# Trepanat_MCU.net
KiCad netlist of a schematic drawn in Altium Designer
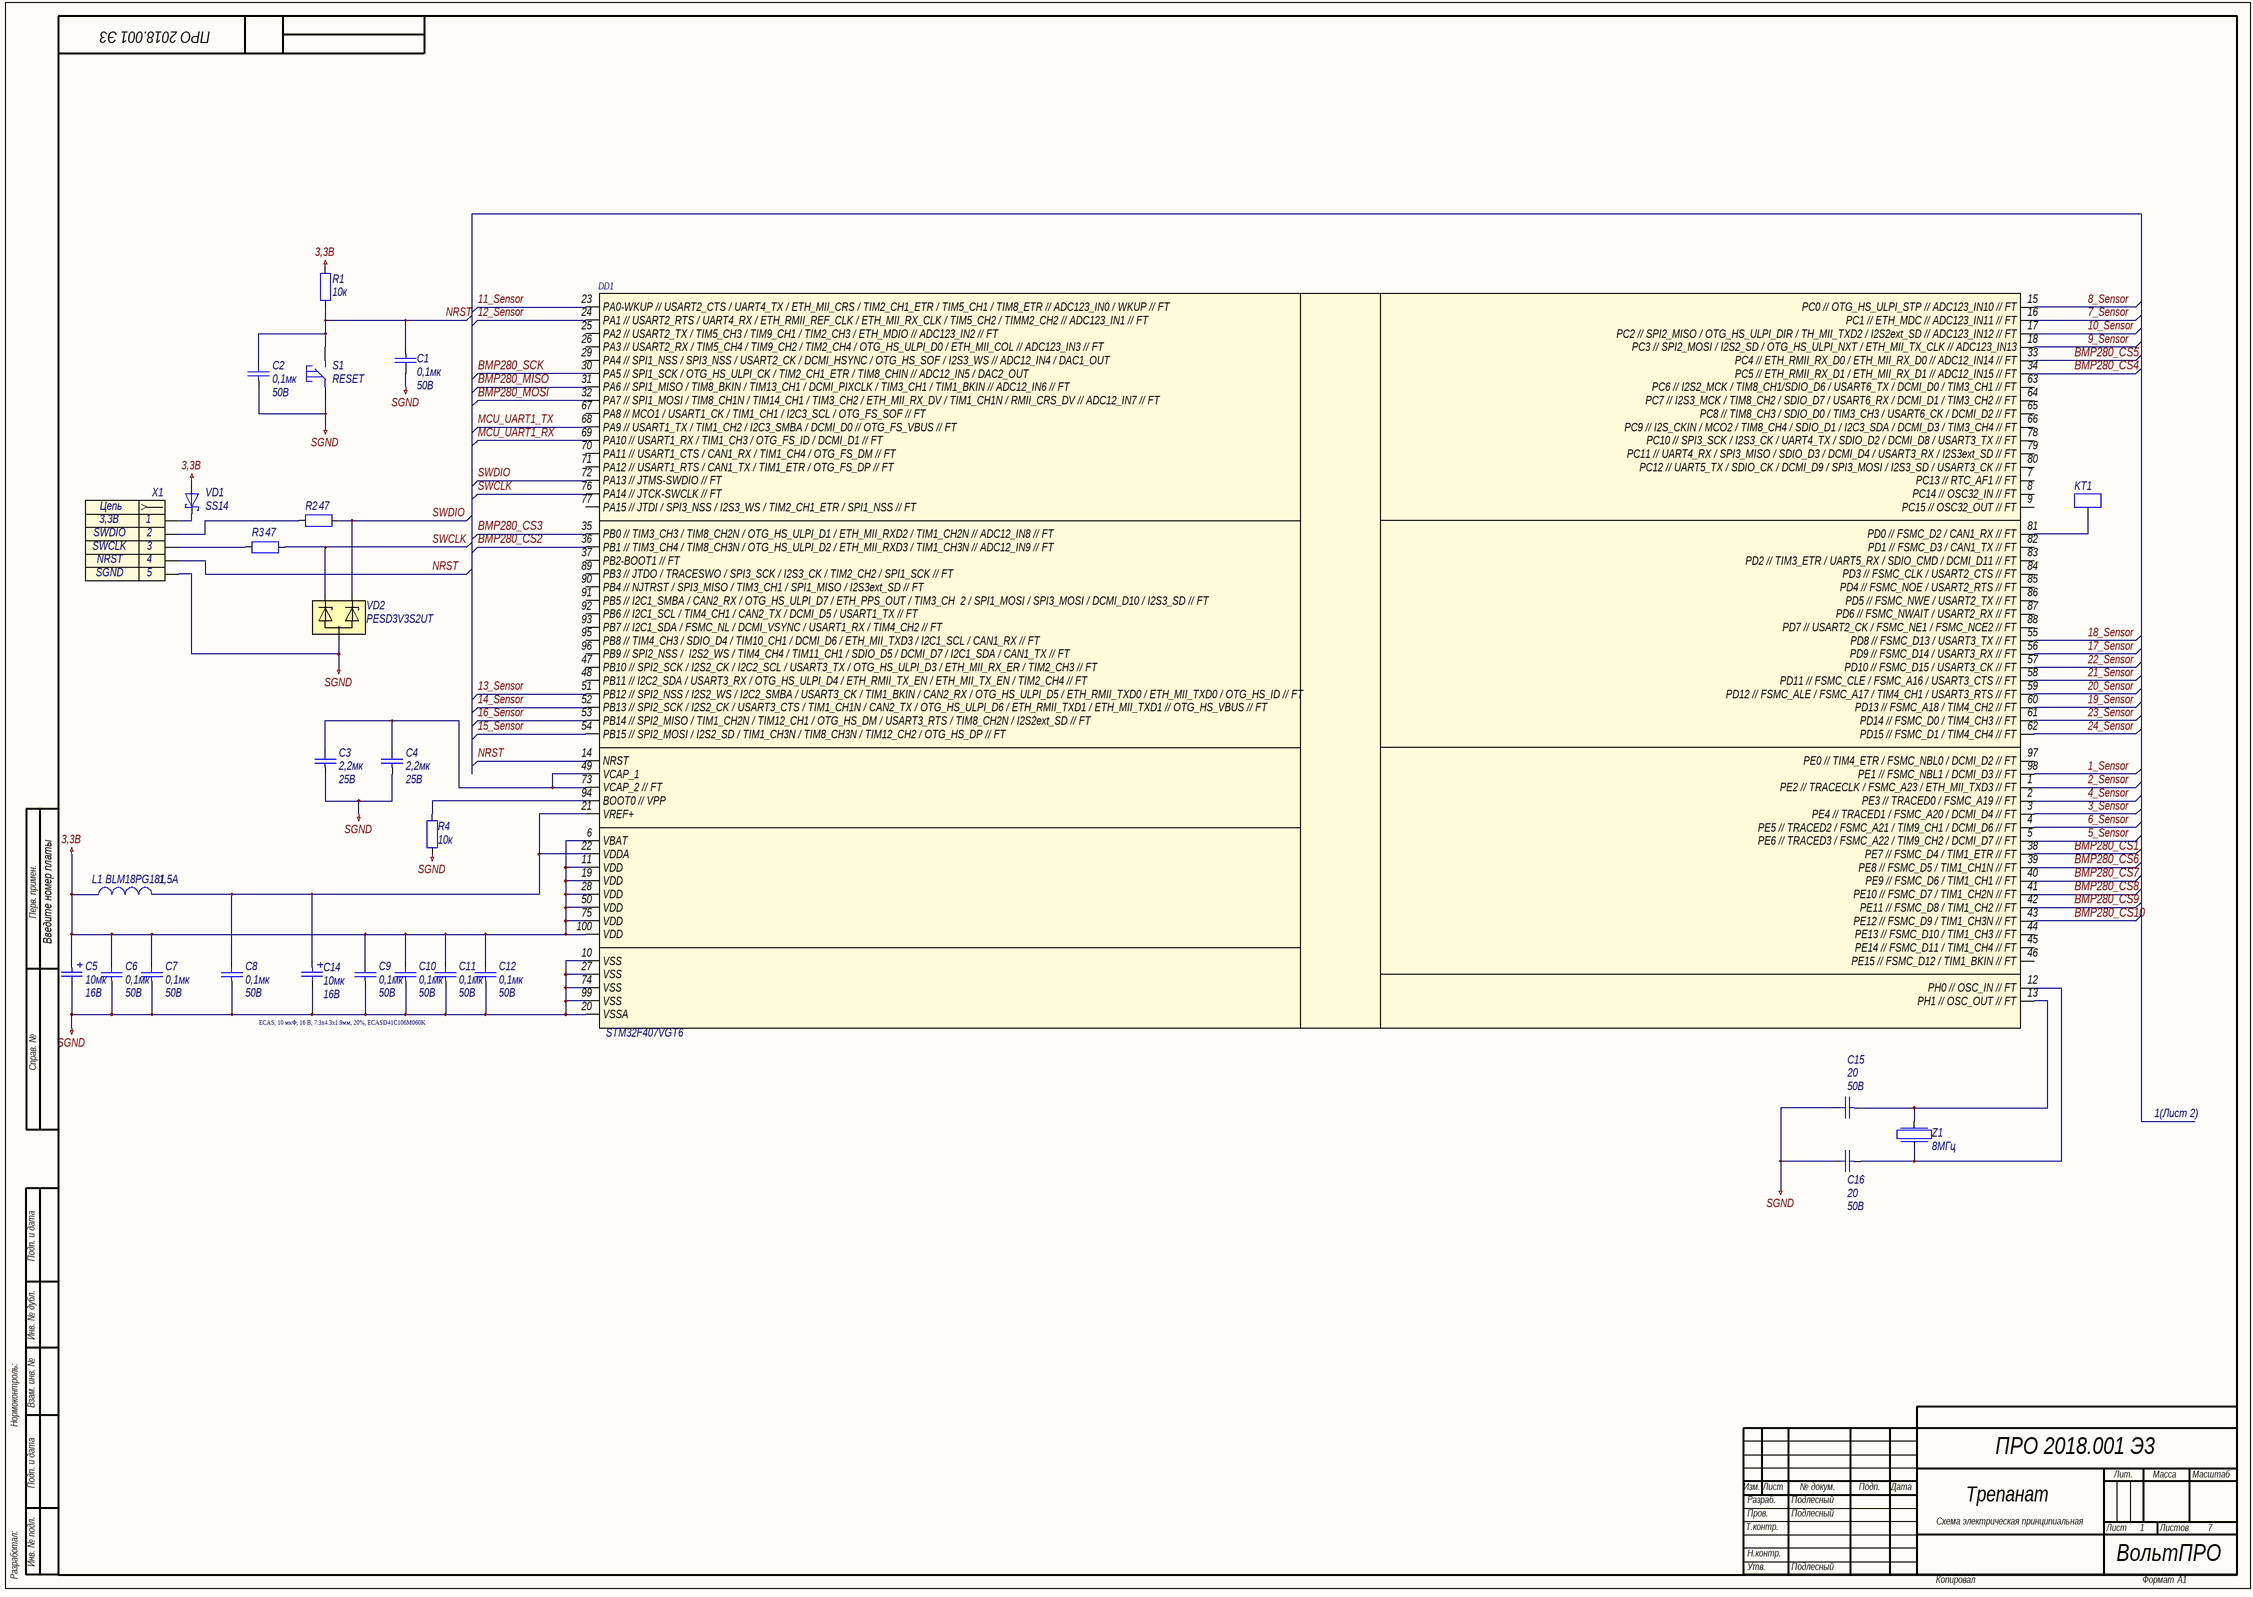
[diagram p0: Trepanat_MCU.SchDoc]

(export (version "E")
  (design (tool "Eeschema 10.0.6"))
  (components
    (comp (ref "C1")
      (value "0,1мк")
      (footprint "ZabugorLib:C0805")
      (description "Конденсатор")
      (fields (field (name "VOLTAGE") "50В"))
      (libsource (lib "ZabugorLib") (part "Capacitor"))
    )
    (comp (ref "C2")
      (value "0,1мк")
      (footprint "ZabugorLib:C0805")
      (description "Конденсатор")
      (fields (field (name "VOLTAGE") "50В"))
      (libsource (lib "ZabugorLib") (part "Capacitor"))
    )
    (comp (ref "C3")
      (value "2,2мк")
      (footprint "ZabugorLib:C0805")
      (description "Конденсатор")
      (fields (field (name "VOLTAGE") "25В"))
      (libsource (lib "ZabugorLib") (part "Capacitor"))
    )
    (comp (ref "C4")
      (value "2,2мк")
      (footprint "ZabugorLib:C0805")
      (description "Конденсатор")
      (fields (field (name "VOLTAGE") "25В"))
      (libsource (lib "ZabugorLib") (part "Capacitor"))
    )
    (comp (ref "C5")
      (value "10мк")
      (footprint "ZabugorLib:TANTAL CASE D")
      (description "Конденсатор полярный")
      (fields (field (name "VOLTAGE") "16В"))
      (libsource (lib "ZabugorLib") (part "Capacitor_pol"))
    )
    (comp (ref "C6")
      (value "0,1мк")
      (footprint "ZabugorLib:C0805")
      (description "Конденсатор")
      (fields (field (name "VOLTAGE") "50В"))
      (libsource (lib "ZabugorLib") (part "Capacitor"))
    )
    (comp (ref "C7")
      (value "0,1мк")
      (footprint "ZabugorLib:C0805")
      (description "Конденсатор")
      (fields (field (name "VOLTAGE") "50В"))
      (libsource (lib "ZabugorLib") (part "Capacitor"))
    )
    (comp (ref "C8")
      (value "0,1мк")
      (footprint "ZabugorLib:C0805")
      (description "Конденсатор")
      (fields (field (name "VOLTAGE") "50В"))
      (libsource (lib "ZabugorLib") (part "Capacitor"))
    )
    (comp (ref "C9")
      (value "0,1мк")
      (footprint "ZabugorLib:C0805")
      (description "Конденсатор")
      (fields (field (name "VOLTAGE") "50В"))
      (libsource (lib "ZabugorLib") (part "Capacitor"))
    )
    (comp (ref "C10")
      (value "0,1мк")
      (footprint "ZabugorLib:C0805")
      (description "Конденсатор")
      (fields (field (name "VOLTAGE") "50В"))
      (libsource (lib "ZabugorLib") (part "Capacitor"))
    )
    (comp (ref "C11")
      (value "0,1мк")
      (footprint "ZabugorLib:C0805")
      (description "Конденсатор")
      (fields (field (name "VOLTAGE") "50В"))
      (libsource (lib "ZabugorLib") (part "Capacitor"))
    )
    (comp (ref "C12")
      (value "0,1мк")
      (footprint "ZabugorLib:C0805")
      (description "Конденсатор")
      (fields (field (name "VOLTAGE") "50В"))
      (libsource (lib "ZabugorLib") (part "Capacitor"))
    )
    (comp (ref "C14")
      (value "10мк")
      (footprint "ZabugorLib:TANTAL CASE D")
      (description "Конденсатор полярный")
      (fields (field (name "VOLTAGE") "16В"))
      (libsource (lib "ZabugorLib") (part "Capacitor_pol"))
    )
    (comp (ref "C15")
      (value "20")
      (footprint "ZabugorLib:C0805")
      (description "Конденсатор")
      (fields (field (name "VOLTAGE") "50В"))
      (libsource (lib "ZabugorLib") (part "Capacitor"))
    )
    (comp (ref "C16")
      (value "20")
      (footprint "ZabugorLib:C0805")
      (description "Конденсатор")
      (fields (field (name "VOLTAGE") "50В"))
      (libsource (lib "ZabugorLib") (part "Capacitor"))
    )
    (comp (ref "DD1")
      (value "~")
      (footprint "ZabugorLib:LQPF100")
      (description "Микроконтроллер")
      (libsource (lib "ZabugorLib") (part "STM32F407VGT6"))
    )
    (comp (ref "KT1")
      (value "KT")
      (footprint "ZabugorLib:КТ")
      (description "Контрольная точка")
      (libsource (lib "ZabugorLib") (part "KT"))
    )
    (comp (ref "L1")
      (value "BLM18PG181")
      (footprint "ZabugorLib:L0603")
      (description "Катушка индуктивности")
      (fields (field (name "IMAX") "1,5A"))
      (libsource (lib "ZabugorLib") (part "Inductor"))
    )
    (comp (ref "R1")
      (value "10к")
      (footprint "ZabugorLib:R0805")
      (description "Резистор")
      (libsource (lib "") (part "Resistor_1"))
    )
    (comp (ref "R2")
      (value "47")
      (footprint "ZabugorLib:R0805")
      (description "Резистор")
      (libsource (lib "ZabugorLib") (part "Resistor"))
    )
    (comp (ref "R3")
      (value "47")
      (footprint "ZabugorLib:R0805")
      (description "Резистор")
      (libsource (lib "ZabugorLib") (part "Resistor"))
    )
    (comp (ref "R4")
      (value "10к")
      (footprint "ZabugorLib:R0805")
      (description "Резистор")
      (libsource (lib "") (part "Resistor_2"))
    )
    (comp (ref "S1")
      (value "RESET")
      (footprint "ZabugorLib:Button_SMD")
      (description "Кнопка")
      (fields (field (name "NAME") "RESET"))
      (libsource (lib "ZabugorLib") (part "Button_SMD"))
    )
    (comp (ref "VD1")
      (value "SS14")
      (footprint "ZabugorLib:SMA")
      (description "Диод Шоттки")
      (libsource (lib "ZabugorLib") (part "DiodeSchottky"))
    )
    (comp (ref "VD2")
      (value "PESD3V3S2UT")
      (footprint "ZabugorLib:SOT23-3")
      (description "Сборка TVS-диодов")
      (fields (field (name "NAME") "PESD3V3S2UT"))
      (libsource (lib "ZabugorLib") (part "PESD3V3S2UT"))
    )
    (comp (ref "X1")
      (value "~")
      (footprint "ZabugorLib:PLS-5")
      (description "Разъем - 4 конт. розетка")
      (libsource (lib "ZabugorLib") (part "Header_5_sct"))
    )
    (comp (ref "Z1")
      (value "8МГц")
      (footprint "ZabugorLib:QSMD5.0x3.2x1.0")
      (description "Кварцевый резонатор")
      (libsource (lib "ZabugorLib") (part "Crystal"))
    )
  )
  (nets
    (net (code "1") (name "/1_Sensor") (class "Default")
      (node (ref "DD1") (pin "98") (pinfunction "PE1_//_FSMC_NBL1_/_DCMI_D3_//_FT_98") (pintype "passive"))
    )
    (net (code "2") (name "/2_Sensor") (class "Default")
      (node (ref "DD1") (pin "1") (pinfunction "PE2_//_TRACECLK_/_FSMC_A23_/_ETH_MII_TXD3_//_FT_1") (pintype "passive"))
    )
    (net (code "3") (name "/3_Sensor") (class "Default")
      (node (ref "DD1") (pin "3") (pinfunction "PE4_//_TRACED1_/_FSMC_A20_/_DCMI_D4_//_FT_3") (pintype "passive"))
    )
    (net (code "4") (name "/4_Sensor") (class "Default")
      (node (ref "DD1") (pin "2") (pinfunction "PE3_//_TRACED0_/_FSMC_A19_//_FT_2") (pintype "passive"))
    )
    (net (code "5") (name "/5_Sensor") (class "Default")
      (node (ref "DD1") (pin "5") (pinfunction "PE6_//_TRACED3_/_FSMC_A22_/_TIM9_CH2_/_DCMI_D7_//_FT_5") (pintype "passive"))
    )
    (net (code "6") (name "/6_Sensor") (class "Default")
      (node (ref "DD1") (pin "4") (pinfunction "PE5_//_TRACED2_/_FSMC_A21_/_TIM9_CH1_/_DCMI_D6_//_FT_4") (pintype "passive"))
    )
    (net (code "7") (name "/7_Sensor") (class "Default")
      (node (ref "DD1") (pin "16") (pinfunction "PC1_//_ETH_MDC_//_ADC123_IN11_//_FT_16") (pintype "passive"))
    )
    (net (code "8") (name "/8_Sensor") (class "Default")
      (node (ref "DD1") (pin "15") (pinfunction "PC0_//_OTG_HS_ULPI_STP_//_ADC123_IN10_//_FT_15") (pintype "passive"))
    )
    (net (code "9") (name "/9_Sensor") (class "Default")
      (node (ref "DD1") (pin "18") (pinfunction "PC3_//_SPI2_MOSI_/_I2S2_SD_/_OTG_HS_ULPI_NXT_/_ETH_MII_TX_CLK_//_ADC123_IN13_18") (pintype "passive"))
    )
    (net (code "10") (name "/10_Sensor") (class "Default")
      (node (ref "DD1") (pin "17") (pinfunction "PC2_//_SPI2_MISO_/_OTG_HS_ULPI_DIR_/_TH_MII_TXD2_/_I2S2ext_SD_//_ADC123_IN12_//_FT_17") (pintype "passive"))
    )
    (net (code "11") (name "/11_Sensor") (class "Default")
      (node (ref "DD1") (pin "23") (pinfunction "PA0-WKUP_//_USART2_CTS_/_UART4_TX_/_ETH_MII_CRS_/_TIM2_CH1_ETR_/_TIM5_CH1_/_TIM8_ETR_//_ADC123_IN0_/_WKUP_//_FT_23") (pintype "passive"))
    )
    (net (code "12") (name "/12_Sensor") (class "Default")
      (node (ref "DD1") (pin "24") (pinfunction "PA1_//_USART2_RTS_/_UART4_RX_/_ETH_RMII_REF_CLK_/_ETH_MII_RX_CLK_/_TIM5_CH2_/_TIMM2_CH2_//_ADC123_IN1_//_FT_24") (pintype "passive"))
    )
    (net (code "13") (name "/13_Sensor") (class "Default")
      (node (ref "DD1") (pin "51") (pinfunction "PB12_//_SPI2_NSS_/_I2S2_WS_/_I2C2_SMBA_/_USART3_CK_/_TIM1_BKIN_/_CAN2_RX_/_OTG_HS_ULPI_D5_/_ETH_RMII_TXD0_/_ETH_MII_TXD0_/_OTG_HS_ID_//_FT_51") (pintype "passive"))
    )
    (net (code "14") (name "/14_Sensor") (class "Default")
      (node (ref "DD1") (pin "52") (pinfunction "PB13_//_SPI2_SCK_/_I2S2_CK_/_USART3_CTS_/_TIM1_CH1N_/_CAN2_TX_/_OTG_HS_ULPI_D6_/_ETH_RMII_TXD1_/_ETH_MII_TXD1_//_OTG_HS_VBUS_//_FT_52") (pintype "passive"))
    )
    (net (code "15") (name "/15_Sensor") (class "Default")
      (node (ref "DD1") (pin "54") (pinfunction "PB15_//_SPI2_MOSI_/_I2S2_SD_/_TIM1_CH3N_/_TIM8_CH3N_/_TIM12_CH2_/_OTG_HS_DP_//_FT_54") (pintype "passive"))
    )
    (net (code "16") (name "/16_Sensor") (class "Default")
      (node (ref "DD1") (pin "53") (pinfunction "PB14_//_SPI2_MISO_/_TIM1_CH2N_/_TIM12_CH1_/_OTG_HS_DM_/_USART3_RTS_/_TIM8_CH2N_/_I2S2ext_SD_//_FT_53") (pintype "passive"))
    )
    (net (code "17") (name "/17_Sensor") (class "Default")
      (node (ref "DD1") (pin "56") (pinfunction "PD9_//_FSMC_D14_/_USART3_RX_//_FT_56") (pintype "passive"))
    )
    (net (code "18") (name "/18_Sensor") (class "Default")
      (node (ref "DD1") (pin "55") (pinfunction "PD8_//_FSMC_D13_/_USART3_TX_//_FT_55") (pintype "passive"))
    )
    (net (code "19") (name "/19_Sensor") (class "Default")
      (node (ref "DD1") (pin "60") (pinfunction "PD13_//_FSMC_A18_/_TIM4_CH2_//_FT_60") (pintype "passive"))
    )
    (net (code "20") (name "/20_Sensor") (class "Default")
      (node (ref "DD1") (pin "59") (pinfunction "PD12_//_FSMC_ALE_/_FSMC_A17_/_TIM4_CH1_/_USART3_RTS_//_FT_59") (pintype "passive"))
    )
    (net (code "21") (name "/21_Sensor") (class "Default")
      (node (ref "DD1") (pin "58") (pinfunction "PD11_//_FSMC_CLE_/_FSMC_A16_/_USART3_CTS_//_FT_58") (pintype "passive"))
    )
    (net (code "22") (name "/22_Sensor") (class "Default")
      (node (ref "DD1") (pin "57") (pinfunction "PD10_//_FSMC_D15_/_USART3_CK_//_FT_57") (pintype "passive"))
    )
    (net (code "23") (name "/23_Sensor") (class "Default")
      (node (ref "DD1") (pin "61") (pinfunction "PD14_//_FSMC_D0_/_TIM4_CH3_//_FT_61") (pintype "passive"))
    )
    (net (code "24") (name "/24_Sensor") (class "Default")
      (node (ref "DD1") (pin "62") (pinfunction "PD15_//_FSMC_D1_/_TIM4_CH4_//_FT_62") (pintype "passive"))
    )
    (net (code "25") (name "/BMP280_CS1") (class "Default")
      (node (ref "DD1") (pin "38") (pinfunction "PE7_//_FSMC_D4_/_TIM1_ETR_//_FT_38") (pintype "passive"))
    )
    (net (code "26") (name "/BMP280_CS2") (class "Default")
      (node (ref "DD1") (pin "36") (pinfunction "PB1_//_TIM3_CH4_/_TIM8_CH3N_/_OTG_HS_ULPI_D2_/_ETH_MII_RXD3_/_TIM1_CH3N_//_ADC12_IN9_//_FT_36") (pintype "passive"))
    )
    (net (code "27") (name "/BMP280_CS3") (class "Default")
      (node (ref "DD1") (pin "35") (pinfunction "PB0_//_TIM3_CH3_/_TIM8_CH2N_/_OTG_HS_ULPI_D1_/_ETH_MII_RXD2_/_TIM1_CH2N_//_ADC12_IN8_//_FT_35") (pintype "passive"))
    )
    (net (code "28") (name "/BMP280_CS4") (class "Default")
      (node (ref "DD1") (pin "34") (pinfunction "PC5_//_ETH_RMII_RX_D1_/_ETH_MII_RX_D1_//_ADC12_IN15_//_FT_34") (pintype "passive"))
    )
    (net (code "29") (name "/BMP280_CS5") (class "Default")
      (node (ref "DD1") (pin "33") (pinfunction "PC4_//_ETH_RMII_RX_D0_/_ETH_MII_RX_D0_//_ADC12_IN14_//_FT_33") (pintype "passive"))
    )
    (net (code "30") (name "/BMP280_CS6") (class "Default")
      (node (ref "DD1") (pin "39") (pinfunction "PE8_//_FSMC_D5_/_TIM1_CH1N_//_FT_39") (pintype "passive"))
    )
    (net (code "31") (name "/BMP280_CS7") (class "Default")
      (node (ref "DD1") (pin "40") (pinfunction "PE9_//_FSMC_D6_/_TIM1_CH1_//_FT_40") (pintype "passive"))
    )
    (net (code "32") (name "/BMP280_CS8") (class "Default")
      (node (ref "DD1") (pin "41") (pinfunction "PE10_//_FSMC_D7_/_TIM1_CH2N_//_FT_41") (pintype "passive"))
    )
    (net (code "33") (name "/BMP280_CS9") (class "Default")
      (node (ref "DD1") (pin "42") (pinfunction "PE11_//_FSMC_D8_/_TIM1_CH2_//_FT_42") (pintype "passive"))
    )
    (net (code "34") (name "/BMP280_CS10") (class "Default")
      (node (ref "DD1") (pin "43") (pinfunction "PE12_//_FSMC_D9_/_TIM1_CH3N_//_FT_43") (pintype "passive"))
    )
    (net (code "35") (name "/BMP280_MISO") (class "Default")
      (node (ref "DD1") (pin "31") (pinfunction "PA6_//_SPI1_MISO_/_TIM8_BKIN_/_TIM13_CH1_/_DCMI_PIXCLK_/_TIM3_CH1_/_TIM1_BKIN_//_ADC12_IN6_//_FT_31") (pintype "passive"))
    )
    (net (code "36") (name "/BMP280_MOSI") (class "Default")
      (node (ref "DD1") (pin "32") (pinfunction "PA7_//_SPI1_MOSI_/_TIM8_CH1N_/_TIM14_CH1_/_TIM3_CH2_/_ETH_MII_RX_DV_/_TIM1_CH1N_/_RMII_CRS_DV_//_ADC12_IN7_//_FT_32") (pintype "passive"))
    )
    (net (code "37") (name "/BMP280_SCK") (class "Default")
      (node (ref "DD1") (pin "30") (pinfunction "PA5_//_SPI1_SCK_/_OTG_HS_ULPI_CK_/_TIM2_CH1_ETR_/_TIM8_CHIN_//_ADC12_IN5_/_DAC2_OUT_30") (pintype "passive"))
    )
    (net (code "38") (name "/MCU_UART1_RX") (class "Default")
      (node (ref "DD1") (pin "69") (pinfunction "PA10_//_USART1_RX_/_TIM1_CH3_/_OTG_FS_ID_/_DCMI_D1_//_FT_69") (pintype "passive"))
    )
    (net (code "39") (name "/MCU_UART1_TX") (class "Default")
      (node (ref "DD1") (pin "68") (pinfunction "PA9_//_USART1_TX_/_TIM1_CH2_/_I2C3_SMBA_/_DCMI_D0_//_OTG_FS_VBUS_//_FT_68") (pintype "passive"))
    )
    (net (code "40") (name "/NRST") (class "Default")
      (node (ref "C1") (pin "1") (pinfunction "1_1") (pintype "passive"))
      (node (ref "C2") (pin "2") (pinfunction "2_2") (pintype "passive"))
      (node (ref "DD1") (pin "14") (pinfunction "NRST_14") (pintype "passive"))
      (node (ref "R1") (pin "1") (pinfunction "1_1") (pintype "passive"))
      (node (ref "S1") (pin "4") (pinfunction "4_4") (pintype "passive"))
      (node (ref "X1") (pin "4") (pinfunction "4_4") (pintype "passive"))
    )
    (net (code "41") (name "/SWCLK") (class "Default")
      (node (ref "DD1") (pin "76") (pinfunction "PA14_//_JTCK-SWCLK_//_FT_76") (pintype "passive"))
      (node (ref "R3") (pin "1") (pinfunction "1_1") (pintype "passive"))
      (node (ref "VD2") (pin "1") (pintype "passive"))
    )
    (net (code "42") (name "/SWDIO") (class "Default")
      (node (ref "DD1") (pin "72") (pinfunction "PA13_//_JTMS-SWDIO_//_FT_72") (pintype "passive"))
      (node (ref "R2") (pin "1") (pinfunction "1_1") (pintype "passive"))
      (node (ref "VD2") (pin "2") (pintype "passive"))
    )
    (net (code "43") (name "3,3B") (class "Default")
      (node (ref "C10") (pin "2") (pinfunction "2_2") (pintype "passive"))
      (node (ref "C11") (pin "2") (pinfunction "2_2") (pintype "passive"))
      (node (ref "C12") (pin "2") (pinfunction "2_2") (pintype "passive"))
      (node (ref "C5") (pin "1") (pinfunction "1_1") (pintype "passive"))
      (node (ref "C6") (pin "2") (pinfunction "2_2") (pintype "passive"))
      (node (ref "C7") (pin "2") (pinfunction "2_2") (pintype "passive"))
      (node (ref "C9") (pin "2") (pinfunction "2_2") (pintype "passive"))
      (node (ref "DD1") (pin "100") (pinfunction "VDD_100") (pintype "passive"))
      (node (ref "DD1") (pin "11") (pinfunction "VDD_11") (pintype "passive"))
      (node (ref "DD1") (pin "19") (pinfunction "VDD_19") (pintype "passive"))
      (node (ref "DD1") (pin "28") (pinfunction "VDD_28") (pintype "passive"))
      (node (ref "DD1") (pin "50") (pinfunction "VDD_50") (pintype "passive"))
      (node (ref "DD1") (pin "6") (pinfunction "VBAT_6") (pintype "passive"))
      (node (ref "DD1") (pin "75") (pinfunction "VDD_75") (pintype "passive"))
      (node (ref "L1") (pin "1") (pinfunction "1_1") (pintype "passive"))
      (node (ref "R1") (pin "2") (pinfunction "2_2") (pintype "passive"))
      (node (ref "VD1") (pin "2") (pinfunction "A_2") (pintype "passive"))
    )
    (net (code "44") (name "Net-(DD1-BOOT0_{slash}{slash}_VPP)") (class "Default")
      (node (ref "DD1") (pin "94") (pinfunction "BOOT0_//_VPP_94") (pintype "passive"))
      (node (ref "R4") (pin "1") (pinfunction "1_1") (pintype "passive"))
    )
    (net (code "45") (name "Net-(DD1-PD0_{slash}{slash}_FSMC_D2_{slash}_CAN1_RX_{slash}{slash}_FT)") (class "Default")
      (node (ref "DD1") (pin "81") (pinfunction "PD0_//_FSMC_D2_/_CAN1_RX_//_FT_81") (pintype "passive"))
      (node (ref "KT1") (pin "1") (pinfunction "1_1") (pintype "passive"))
    )
    (net (code "46") (name "Net-(DD1-PH0_{slash}{slash}_OSC_IN_{slash}{slash}_FT)") (class "Default")
      (node (ref "C16") (pin "1") (pinfunction "1_1") (pintype "passive"))
      (node (ref "DD1") (pin "12") (pinfunction "PH0_//_OSC_IN_//_FT_12") (pintype "passive"))
      (node (ref "Z1") (pin "1") (pinfunction "1_1") (pintype "passive"))
    )
    (net (code "47") (name "Net-(DD1-PH1_{slash}{slash}_OSC_OUT_{slash}{slash}_FT)") (class "Default")
      (node (ref "C15") (pin "1") (pinfunction "1_1") (pintype "passive"))
      (node (ref "DD1") (pin "13") (pinfunction "PH1_//_OSC_OUT_//_FT_13") (pintype "passive"))
      (node (ref "Z1") (pin "2") (pinfunction "2_2") (pintype "passive"))
    )
    (net (code "48") (name "Net-(DD1-VCAP_1)") (class "Default")
      (node (ref "C3") (pin "2") (pinfunction "2_2") (pintype "passive"))
      (node (ref "C4") (pin "2") (pinfunction "2_2") (pintype "passive"))
      (node (ref "DD1") (pin "49") (pinfunction "VCAP_1_49") (pintype "passive"))
      (node (ref "DD1") (pin "73") (pinfunction "VCAP_2_//_FT_73") (pintype "passive"))
    )
    (net (code "49") (name "Net-(DD1-VDDA)") (class "Default")
      (node (ref "C14") (pin "1") (pinfunction "1_1") (pintype "passive"))
      (node (ref "C8") (pin "2") (pinfunction "2_2") (pintype "passive"))
      (node (ref "DD1") (pin "21") (pinfunction "VREF+_21") (pintype "passive"))
      (node (ref "DD1") (pin "22") (pinfunction "VDDA_22") (pintype "passive"))
      (node (ref "L1") (pin "2") (pinfunction "2_2") (pintype "passive"))
    )
    (net (code "50") (name "Net-(R2-Pad2)") (class "Default")
      (node (ref "R2") (pin "2") (pinfunction "2_2") (pintype "passive"))
      (node (ref "X1") (pin "2") (pinfunction "2_2") (pintype "passive"))
    )
    (net (code "51") (name "Net-(R3-Pad2)") (class "Default")
      (node (ref "R3") (pin "2") (pinfunction "2_2") (pintype "passive"))
      (node (ref "X1") (pin "3") (pinfunction "3_3") (pintype "passive"))
    )
    (net (code "52") (name "Net-(VD1-K)") (class "Default")
      (node (ref "VD1") (pin "1") (pinfunction "K_1") (pintype "passive"))
      (node (ref "X1") (pin "1") (pinfunction "1_1") (pintype "passive"))
    )
    (net (code "53") (name "SGND") (class "Default")
      (node (ref "C1") (pin "2") (pinfunction "2_2") (pintype "passive"))
      (node (ref "C10") (pin "1") (pinfunction "1_1") (pintype "passive"))
      (node (ref "C11") (pin "1") (pinfunction "1_1") (pintype "passive"))
      (node (ref "C12") (pin "1") (pinfunction "1_1") (pintype "passive"))
      (node (ref "C14") (pin "2") (pinfunction "2_2") (pintype "passive"))
      (node (ref "C15") (pin "2") (pinfunction "2_2") (pintype "passive"))
      (node (ref "C16") (pin "2") (pinfunction "2_2") (pintype "passive"))
      (node (ref "C2") (pin "1") (pinfunction "1_1") (pintype "passive"))
      (node (ref "C3") (pin "1") (pinfunction "1_1") (pintype "passive"))
      (node (ref "C4") (pin "1") (pinfunction "1_1") (pintype "passive"))
      (node (ref "C5") (pin "2") (pinfunction "2_2") (pintype "passive"))
      (node (ref "C6") (pin "1") (pinfunction "1_1") (pintype "passive"))
      (node (ref "C7") (pin "1") (pinfunction "1_1") (pintype "passive"))
      (node (ref "C8") (pin "1") (pinfunction "1_1") (pintype "passive"))
      (node (ref "C9") (pin "1") (pinfunction "1_1") (pintype "passive"))
      (node (ref "DD1") (pin "10") (pinfunction "VSS_10") (pintype "passive"))
      (node (ref "DD1") (pin "20") (pinfunction "VSSA_20") (pintype "passive"))
      (node (ref "DD1") (pin "27") (pinfunction "VSS_27") (pintype "passive"))
      (node (ref "DD1") (pin "74") (pinfunction "VSS_74") (pintype "passive"))
      (node (ref "DD1") (pin "99") (pinfunction "VSS_99") (pintype "passive"))
      (node (ref "R4") (pin "2") (pinfunction "2_2") (pintype "passive"))
      (node (ref "S1") (pin "1") (pinfunction "1_1") (pintype "passive"))
      (node (ref "VD2") (pin "3") (pintype "passive"))
      (node (ref "X1") (pin "5") (pinfunction "5_5") (pintype "passive"))
    )
    (net (code "54") (name "unconnected-(DD1-PA2_{slash}{slash}_USART2_TX_{slash}_TIM5_CH3_{slash}_TIM9_CH1_{slash}_TIM2_CH3_{slash}_ETH_MDIO_{slash}{slash}_ADC123_IN2_{slash}{slash}_FT-Pad25)") (class "Default")
      (node (ref "DD1") (pin "25") (pinfunction "PA2_//_USART2_TX_/_TIM5_CH3_/_TIM9_CH1_/_TIM2_CH3_/_ETH_MDIO_//_ADC123_IN2_//_FT_25") (pintype "passive"))
    )
    (net (code "55") (name "unconnected-(DD1-PA3_{slash}{slash}_USART2_RX_{slash}_TIM5_CH4_{slash}_TIM9_CH2_{slash}_TIM2_CH4_{slash}_OTG_HS_ULPI_D0_{slash}_ETH_MII_COL_{slash}{slash}_ADC123_IN3_{slash}{slash}_FT-Pad26)") (class "Default")
      (node (ref "DD1") (pin "26") (pinfunction "PA3_//_USART2_RX_/_TIM5_CH4_/_TIM9_CH2_/_TIM2_CH4_/_OTG_HS_ULPI_D0_/_ETH_MII_COL_//_ADC123_IN3_//_FT_26") (pintype "passive"))
    )
    (net (code "56") (name "unconnected-(DD1-PA4_{slash}{slash}_SPI1_NSS_{slash}_SPI3_NSS_{slash}_USART2_CK_{slash}_DCMI_HSYNC_{slash}_OTG_HS_SOF_{slash}_I2S3_WS_{slash}{slash}_ADC12_IN4_{slash}_DAC1_OUT-Pad29)") (class "Default")
      (node (ref "DD1") (pin "29") (pinfunction "PA4_//_SPI1_NSS_/_SPI3_NSS_/_USART2_CK_/_DCMI_HSYNC_/_OTG_HS_SOF_/_I2S3_WS_//_ADC12_IN4_/_DAC1_OUT_29") (pintype "passive"))
    )
    (net (code "57") (name "unconnected-(DD1-PA8_{slash}{slash}_MCO1_{slash}_USART1_CK_{slash}_TIM1_CH1_{slash}_I2C3_SCL_{slash}_OTG_FS_SOF_{slash}{slash}_FT-Pad67)") (class "Default")
      (node (ref "DD1") (pin "67") (pinfunction "PA8_//_MCO1_/_USART1_CK_/_TIM1_CH1_/_I2C3_SCL_/_OTG_FS_SOF_//_FT_67") (pintype "passive"))
    )
    (net (code "58") (name "unconnected-(DD1-PA11_{slash}{slash}_USART1_CTS_{slash}_CAN1_RX_{slash}_TIM1_CH4_{slash}_OTG_FS_DM_{slash}{slash}_FT-Pad70)") (class "Default")
      (node (ref "DD1") (pin "70") (pinfunction "PA11_//_USART1_CTS_/_CAN1_RX_/_TIM1_CH4_/_OTG_FS_DM_//_FT_70") (pintype "passive"))
    )
    (net (code "59") (name "unconnected-(DD1-PA12_{slash}{slash}_USART1_RTS_{slash}_CAN1_TX_{slash}_TIM1_ETR_{slash}_OTG_FS_DP_{slash}{slash}_FT-Pad71)") (class "Default")
      (node (ref "DD1") (pin "71") (pinfunction "PA12_//_USART1_RTS_/_CAN1_TX_/_TIM1_ETR_/_OTG_FS_DP_//_FT_71") (pintype "passive"))
    )
    (net (code "60") (name "unconnected-(DD1-PA15_{slash}{slash}_JTDI_{slash}_SPI3_NSS_{slash}_I2S3_WS_{slash}_TIM2_CH1_ETR_{slash}_SPI1_NSS_{slash}{slash}_FT-Pad77)") (class "Default")
      (node (ref "DD1") (pin "77") (pinfunction "PA15_//_JTDI_/_SPI3_NSS_/_I2S3_WS_/_TIM2_CH1_ETR_/_SPI1_NSS_//_FT_77") (pintype "passive"))
    )
    (net (code "61") (name "unconnected-(DD1-PB2-BOOT1_{slash}{slash}_FT-Pad37)") (class "Default")
      (node (ref "DD1") (pin "37") (pinfunction "PB2-BOOT1_//_FT_37") (pintype "passive"))
    )
    (net (code "62") (name "unconnected-(DD1-PB3_{slash}{slash}_JTDO_{slash}_TRACESWO_{slash}_SPI3_SCK_{slash}_I2S3_CK_{slash}_TIM2_CH2_{slash}_SPI1_SCK_{slash}{slash}_FT-Pad89)") (class "Default")
      (node (ref "DD1") (pin "89") (pinfunction "PB3_//_JTDO_/_TRACESWO_/_SPI3_SCK_/_I2S3_CK_/_TIM2_CH2_/_SPI1_SCK_//_FT_89") (pintype "passive"))
    )
    (net (code "63") (name "unconnected-(DD1-PB4_{slash}{slash}_NJTRST_{slash}_SPI3_MISO_{slash}_TIM3_CH1_{slash}_SPI1_MISO_{slash}_I2S3ext_SD_{slash}{slash}_FT-Pad90)") (class "Default")
      (node (ref "DD1") (pin "90") (pinfunction "PB4_//_NJTRST_/_SPI3_MISO_/_TIM3_CH1_/_SPI1_MISO_/_I2S3ext_SD_//_FT_90") (pintype "passive"))
    )
    (net (code "64") (name "unconnected-(DD1-PB5_{slash}{slash}_I2C1_SMBA_{slash}_CAN2_RX_{slash}_OTG_HS_ULPI_D7_{slash}_ETH_PPS_OUT_{slash}_TIM3_CH__2_{slash}_SPI1_MOSI_{slash}_SPI3_MOSI_{slash}_DCMI_D10_{slash}_I2S3_SD_{slash}{slash}_FT-Pad91)") (class "Default")
      (node (ref "DD1") (pin "91") (pinfunction "PB5_//_I2C1_SMBA_/_CAN2_RX_/_OTG_HS_ULPI_D7_/_ETH_PPS_OUT_/_TIM3_CH__2_/_SPI1_MOSI_/_SPI3_MOSI_/_DCMI_D10_/_I2S3_SD_//_FT_91") (pintype "passive"))
    )
    (net (code "65") (name "unconnected-(DD1-PB6_{slash}{slash}_I2C1_SCL_{slash}_TIM4_CH1_{slash}_CAN2_TX_{slash}_DCMI_D5_{slash}_USART1_TX_{slash}{slash}_FT-Pad92)") (class "Default")
      (node (ref "DD1") (pin "92") (pinfunction "PB6_//_I2C1_SCL_/_TIM4_CH1_/_CAN2_TX_/_DCMI_D5_/_USART1_TX_//_FT_92") (pintype "passive"))
    )
    (net (code "66") (name "unconnected-(DD1-PB7_{slash}{slash}_I2C1_SDA_{slash}_FSMC_NL_{slash}_DCMI_VSYNC_{slash}_USART1_RX_{slash}_TIM4_CH2_{slash}{slash}_FT-Pad93)") (class "Default")
      (node (ref "DD1") (pin "93") (pinfunction "PB7_//_I2C1_SDA_/_FSMC_NL_/_DCMI_VSYNC_/_USART1_RX_/_TIM4_CH2_//_FT_93") (pintype "passive"))
    )
    (net (code "67") (name "unconnected-(DD1-PB8_{slash}{slash}_TIM4_CH3_{slash}_SDIO_D4_{slash}_TIM10_CH1_{slash}_DCMI_D6_{slash}_ETH_MII_TXD3_{slash}_I2C1_SCL_{slash}_CAN1_RX_{slash}{slash}_FT-Pad95)") (class "Default")
      (node (ref "DD1") (pin "95") (pinfunction "PB8_//_TIM4_CH3_/_SDIO_D4_/_TIM10_CH1_/_DCMI_D6_/_ETH_MII_TXD3_/_I2C1_SCL_/_CAN1_RX_//_FT_95") (pintype "passive"))
    )
    (net (code "68") (name "unconnected-(DD1-PB9_{slash}{slash}_SPI2_NSS_{slash}__I2S2_WS_{slash}_TIM4_CH4_{slash}_TIM11_CH1_{slash}_SDIO_D5_{slash}_DCMI_D7_{slash}_I2C1_SDA_{slash}_CAN1_TX_{slash}{slash}_FT-Pad96)") (class "Default")
      (node (ref "DD1") (pin "96") (pinfunction "PB9_//_SPI2_NSS_/__I2S2_WS_/_TIM4_CH4_/_TIM11_CH1_/_SDIO_D5_/_DCMI_D7_/_I2C1_SDA_/_CAN1_TX_//_FT_96") (pintype "passive"))
    )
    (net (code "69") (name "unconnected-(DD1-PB10_{slash}{slash}_SPI2_SCK_{slash}_I2S2_CK_{slash}_I2C2_SCL_{slash}_USART3_TX_{slash}_OTG_HS_ULPI_D3_{slash}_ETH_MII_RX_ER_{slash}_TIM2_CH3_{slash}{slash}_FT-Pad47)") (class "Default")
      (node (ref "DD1") (pin "47") (pinfunction "PB10_//_SPI2_SCK_/_I2S2_CK_/_I2C2_SCL_/_USART3_TX_/_OTG_HS_ULPI_D3_/_ETH_MII_RX_ER_/_TIM2_CH3_//_FT_47") (pintype "passive"))
    )
    (net (code "70") (name "unconnected-(DD1-PB11_{slash}{slash}_I2C2_SDA_{slash}_USART3_RX_{slash}_OTG_HS_ULPI_D4_{slash}_ETH_RMII_TX_EN_{slash}_ETH_MII_TX_EN_{slash}_TIM2_CH4_{slash}{slash}_FT-Pad48)") (class "Default")
      (node (ref "DD1") (pin "48") (pinfunction "PB11_//_I2C2_SDA_/_USART3_RX_/_OTG_HS_ULPI_D4_/_ETH_RMII_TX_EN_/_ETH_MII_TX_EN_/_TIM2_CH4_//_FT_48") (pintype "passive"))
    )
    (net (code "71") (name "unconnected-(DD1-PC6_{slash}{slash}_I2S2_MCK_{slash}_TIM8_CH1{slash}SDIO_D6_{slash}_USART6_TX_{slash}_DCMI_D0_{slash}_TIM3_CH1_{slash}{slash}_FT-Pad63)") (class "Default")
      (node (ref "DD1") (pin "63") (pinfunction "PC6_//_I2S2_MCK_/_TIM8_CH1/SDIO_D6_/_USART6_TX_/_DCMI_D0_/_TIM3_CH1_//_FT_63") (pintype "passive"))
    )
    (net (code "72") (name "unconnected-(DD1-PC7_{slash}{slash}_I2S3_MCK_{slash}_TIM8_CH2_{slash}_SDIO_D7_{slash}_USART6_RX_{slash}_DCMI_D1_{slash}_TIM3_CH2_{slash}{slash}_FT-Pad64)") (class "Default")
      (node (ref "DD1") (pin "64") (pinfunction "PC7_//_I2S3_MCK_/_TIM8_CH2_/_SDIO_D7_/_USART6_RX_/_DCMI_D1_/_TIM3_CH2_//_FT_64") (pintype "passive"))
    )
    (net (code "73") (name "unconnected-(DD1-PC8_{slash}{slash}_TIM8_CH3_{slash}_SDIO_D0_{slash}_TIM3_CH3_{slash}_USART6_CK_{slash}_DCMI_D2_{slash}{slash}_FT-Pad65)") (class "Default")
      (node (ref "DD1") (pin "65") (pinfunction "PC8_//_TIM8_CH3_/_SDIO_D0_/_TIM3_CH3_/_USART6_CK_/_DCMI_D2_//_FT_65") (pintype "passive"))
    )
    (net (code "74") (name "unconnected-(DD1-PC9_{slash}{slash}_I2S_CKIN_{slash}_MCO2_{slash}_TIM8_CH4_{slash}_SDIO_D1_{slash}_I2C3_SDA_{slash}_DCMI_D3_{slash}_TIM3_CH4_{slash}{slash}_FT-Pad66)") (class "Default")
      (node (ref "DD1") (pin "66") (pinfunction "PC9_//_I2S_CKIN_/_MCO2_/_TIM8_CH4_/_SDIO_D1_/_I2C3_SDA_/_DCMI_D3_/_TIM3_CH4_//_FT_66") (pintype "passive"))
    )
    (net (code "75") (name "unconnected-(DD1-PC10_{slash}{slash}_SPI3_SCK_{slash}_I2S3_CK_{slash}_UART4_TX_{slash}_SDIO_D2_{slash}_DCMI_D8_{slash}_USART3_TX_{slash}{slash}_FT-Pad78)") (class "Default")
      (node (ref "DD1") (pin "78") (pinfunction "PC10_//_SPI3_SCK_/_I2S3_CK_/_UART4_TX_/_SDIO_D2_/_DCMI_D8_/_USART3_TX_//_FT_78") (pintype "passive"))
    )
    (net (code "76") (name "unconnected-(DD1-PC11_{slash}{slash}_UART4_RX_{slash}_SPI3_MISO_{slash}_SDIO_D3_{slash}_DCMI_D4_{slash}_USART3_RX_{slash}_I2S3ext_SD_{slash}{slash}_FT-Pad79)") (class "Default")
      (node (ref "DD1") (pin "79") (pinfunction "PC11_//_UART4_RX_/_SPI3_MISO_/_SDIO_D3_/_DCMI_D4_/_USART3_RX_/_I2S3ext_SD_//_FT_79") (pintype "passive"))
    )
    (net (code "77") (name "unconnected-(DD1-PC12_{slash}{slash}_UART5_TX_{slash}_SDIO_CK_{slash}_DCMI_D9_{slash}_SPI3_MOSI_{slash}_I2S3_SD_{slash}_USART3_CK_{slash}{slash}_FT-Pad80)") (class "Default")
      (node (ref "DD1") (pin "80") (pinfunction "PC12_//_UART5_TX_/_SDIO_CK_/_DCMI_D9_/_SPI3_MOSI_/_I2S3_SD_/_USART3_CK_//_FT_80") (pintype "passive"))
    )
    (net (code "78") (name "unconnected-(DD1-PC13_{slash}{slash}_RTC_AF1_{slash}{slash}_FT-Pad7)") (class "Default")
      (node (ref "DD1") (pin "7") (pinfunction "PC13_//_RTC_AF1_//_FT_7") (pintype "passive"))
    )
    (net (code "79") (name "unconnected-(DD1-PC14_{slash}{slash}_OSC32_IN_{slash}{slash}_FT-Pad8)") (class "Default")
      (node (ref "DD1") (pin "8") (pinfunction "PC14_//_OSC32_IN_//_FT_8") (pintype "passive"))
    )
    (net (code "80") (name "unconnected-(DD1-PC15_{slash}{slash}_OSC32_OUT_{slash}{slash}_FT-Pad9)") (class "Default")
      (node (ref "DD1") (pin "9") (pinfunction "PC15_//_OSC32_OUT_//_FT_9") (pintype "passive"))
    )
    (net (code "81") (name "unconnected-(DD1-PD1_{slash}{slash}_FSMC_D3_{slash}_CAN1_TX_{slash}{slash}_FT-Pad82)") (class "Default")
      (node (ref "DD1") (pin "82") (pinfunction "PD1_//_FSMC_D3_/_CAN1_TX_//_FT_82") (pintype "passive"))
    )
    (net (code "82") (name "unconnected-(DD1-PD2_{slash}{slash}_TIM3_ETR_{slash}_UART5_RX_{slash}_SDIO_CMD_{slash}_DCMI_D11_{slash}{slash}_FT-Pad83)") (class "Default")
      (node (ref "DD1") (pin "83") (pinfunction "PD2_//_TIM3_ETR_/_UART5_RX_/_SDIO_CMD_/_DCMI_D11_//_FT_83") (pintype "passive"))
    )
    (net (code "83") (name "unconnected-(DD1-PD3_{slash}{slash}_FSMC_CLK_{slash}_USART2_CTS_{slash}{slash}_FT-Pad84)") (class "Default")
      (node (ref "DD1") (pin "84") (pinfunction "PD3_//_FSMC_CLK_/_USART2_CTS_//_FT_84") (pintype "passive"))
    )
    (net (code "84") (name "unconnected-(DD1-PD4_{slash}{slash}_FSMC_NOE_{slash}_USART2_RTS_{slash}{slash}_FT-Pad85)") (class "Default")
      (node (ref "DD1") (pin "85") (pinfunction "PD4_//_FSMC_NOE_/_USART2_RTS_//_FT_85") (pintype "passive"))
    )
    (net (code "85") (name "unconnected-(DD1-PD5_{slash}{slash}_FSMC_NWE_{slash}_USART2_TX_{slash}{slash}_FT-Pad86)") (class "Default")
      (node (ref "DD1") (pin "86") (pinfunction "PD5_//_FSMC_NWE_/_USART2_TX_//_FT_86") (pintype "passive"))
    )
    (net (code "86") (name "unconnected-(DD1-PD6_{slash}{slash}_FSMC_NWAIT_{slash}_USART2_RX_{slash}{slash}_FT-Pad87)") (class "Default")
      (node (ref "DD1") (pin "87") (pinfunction "PD6_//_FSMC_NWAIT_/_USART2_RX_//_FT_87") (pintype "passive"))
    )
    (net (code "87") (name "unconnected-(DD1-PD7_{slash}{slash}_USART2_CK_{slash}_FSMC_NE1_{slash}_FSMC_NCE2_{slash}{slash}_FT-Pad88)") (class "Default")
      (node (ref "DD1") (pin "88") (pinfunction "PD7_//_USART2_CK_/_FSMC_NE1_/_FSMC_NCE2_//_FT_88") (pintype "passive"))
    )
    (net (code "88") (name "unconnected-(DD1-PE0_{slash}{slash}_TIM4_ETR_{slash}_FSMC_NBL0_{slash}_DCMI_D2_{slash}{slash}_FT-Pad97)") (class "Default")
      (node (ref "DD1") (pin "97") (pinfunction "PE0_//_TIM4_ETR_/_FSMC_NBL0_/_DCMI_D2_//_FT_97") (pintype "passive"))
    )
    (net (code "89") (name "unconnected-(DD1-PE13_{slash}{slash}_FSMC_D10_{slash}_TIM1_CH3_{slash}{slash}_FT-Pad44)") (class "Default")
      (node (ref "DD1") (pin "44") (pinfunction "PE13_//_FSMC_D10_/_TIM1_CH3_//_FT_44") (pintype "passive"))
    )
    (net (code "90") (name "unconnected-(DD1-PE14_{slash}{slash}_FSMC_D11_{slash}_TIM1_CH4_{slash}{slash}_FT-Pad45)") (class "Default")
      (node (ref "DD1") (pin "45") (pinfunction "PE14_//_FSMC_D11_/_TIM1_CH4_//_FT_45") (pintype "passive"))
    )
    (net (code "91") (name "unconnected-(DD1-PE15_{slash}{slash}_FSMC_D12_{slash}_TIM1_BKIN_{slash}{slash}_FT-Pad46)") (class "Default")
      (node (ref "DD1") (pin "46") (pinfunction "PE15_//_FSMC_D12_/_TIM1_BKIN_//_FT_46") (pintype "passive"))
    )
  )
)
